# WIFIBT_AP6398S.net
KiCad netlist of a schematic drawn in Altium Designer
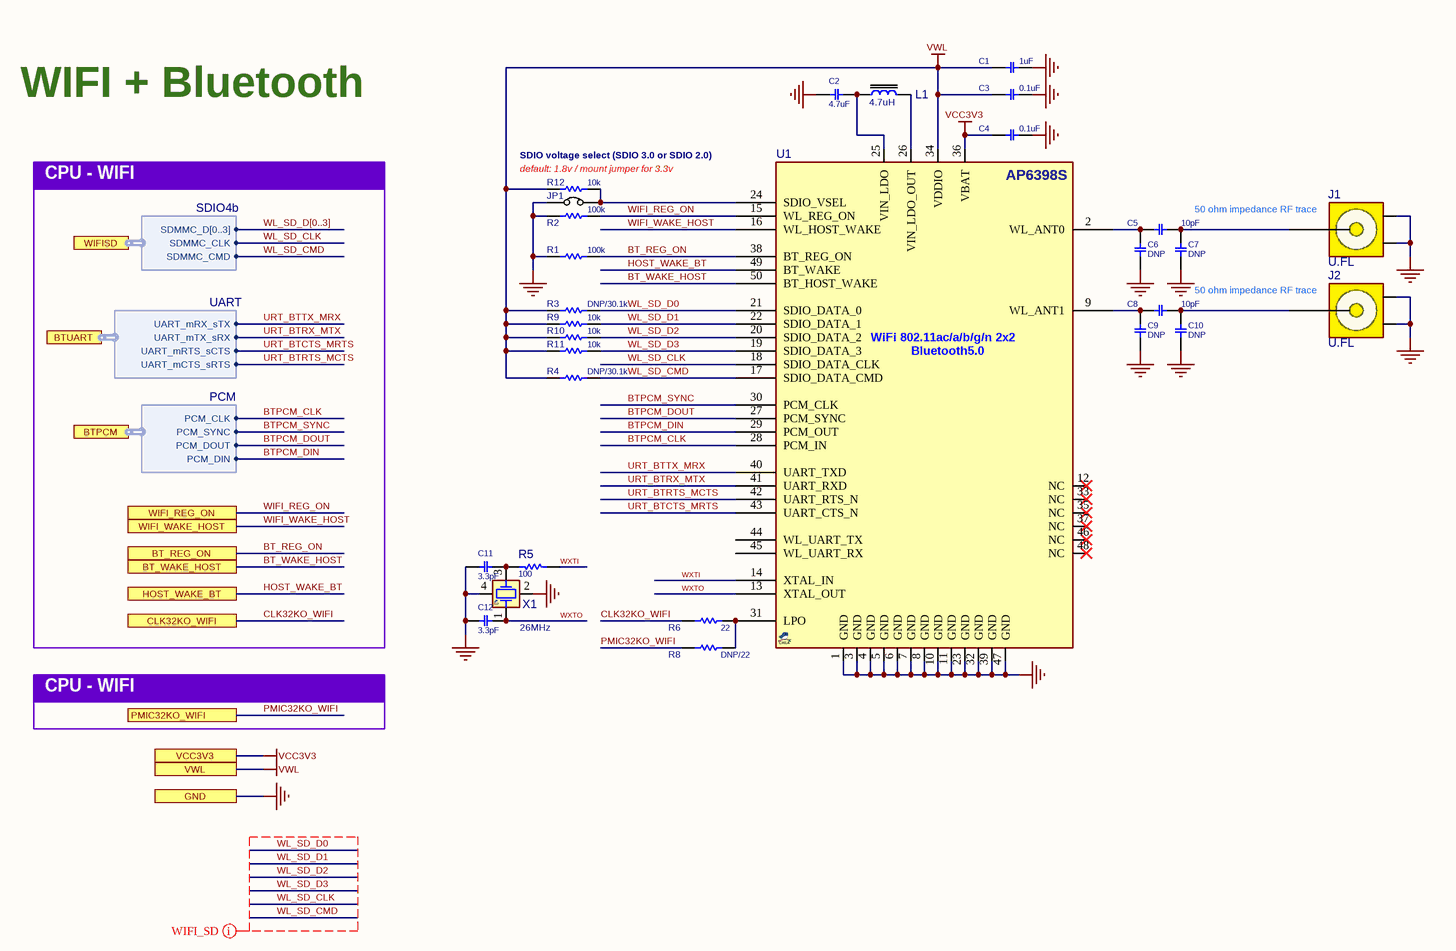
[diagram p0: WIFIBT_AP6398S.SchDoc]

(export (version "E")
  (design (tool "Eeschema 10.0.6"))
  (components
    (comp (ref "C1")
      (value "1uF")
      (footprint "C0402")
      (description "CAP, MLCC")
      (fields (field (name "MANF_P#") "CL05A105KO5NNND") (field (name "MANF") "Samsung"))
      (libsource (lib "passive_smd") (part "CAP_SMD_MLCC"))
    )
    (comp (ref "C2")
      (value "4.7uF")
      (footprint "C0402")
      (description "CAP, MLCC")
      (fields (field (name "MANF_P#") "LMK105BBJ475MVLF") (field (name "MANF") "Taiyo Yuden"))
      (libsource (lib "passive_smd") (part "CAP_SMD_MLCC"))
    )
    (comp (ref "C3")
      (value "0.1uF")
      (footprint "C0402")
      (description "CAP, MLCC")
      (fields (field (name "MANF_P#") "GRM155R61E104") (field (name "MANF") "Murata"))
      (libsource (lib "passive_smd") (part "CAP_SMD_MLCC"))
    )
    (comp (ref "C4")
      (value "0.1uF")
      (footprint "C0402")
      (description "CAP, MLCC")
      (fields (field (name "MANF_P#") "GRM155R61E104") (field (name "MANF") "Murata"))
      (libsource (lib "passive_smd") (part "CAP_SMD_MLCC"))
    )
    (comp (ref "C5")
      (value "10pF")
      (footprint "C0402")
      (description "CAP, MLCC")
      (fields (field (name "MANF_P#") "CC0402JRNPO9BN100") (field (name "MANF") "YAGEO"))
      (libsource (lib "passive_smd") (part "CAP_SMD_MLCC"))
    )
    (comp (ref "C6")
      (value "DNP")
      (footprint "C0402")
      (description "CAP, MLCC, 1nF, 50V, C0G, 10%, 0402")
      (libsource (lib "passive_smd") (part "CAP_SMD_MLCC"))
    )
    (comp (ref "C7")
      (value "DNP")
      (footprint "C0402")
      (description "CAP, MLCC, 1nF, 50V, C0G, 10%, 0402")
      (libsource (lib "passive_smd") (part "CAP_SMD_MLCC"))
    )
    (comp (ref "C8")
      (value "10pF")
      (footprint "C0402")
      (description "CAP, MLCC")
      (fields (field (name "MANF_P#") "CC0402JRNPO9BN100") (field (name "MANF") "YAGEO"))
      (libsource (lib "passive_smd") (part "CAP_SMD_MLCC"))
    )
    (comp (ref "C9")
      (value "DNP")
      (footprint "C0402")
      (description "CAP, MLCC, 1nF, 50V, C0G, 10%, 0402")
      (libsource (lib "passive_smd") (part "CAP_SMD_MLCC"))
    )
    (comp (ref "C10")
      (value "DNP")
      (footprint "C0402")
      (description "CAP, MLCC, 1nF, 50V, C0G, 10%, 0402")
      (libsource (lib "passive_smd") (part "CAP_SMD_MLCC"))
    )
    (comp (ref "C11")
      (value "3.3pF")
      (footprint "C0402")
      (description "CAP, MLCC")
      (fields (field (name "MANF_P#") "CC0402CRNPO9BN3R3") (field (name "MANF") "Yageo"))
      (libsource (lib "passive_smd") (part "CAP_SMD_MLCC"))
    )
    (comp (ref "C12")
      (value "3.3pF")
      (footprint "C0402")
      (description "CAP, MLCC")
      (fields (field (name "MANF_P#") "CC0402CRNPO9BN3R3") (field (name "MANF") "Yageo"))
      (libsource (lib "passive_smd") (part "CAP_SMD_MLCC"))
    )
    (comp (ref "J1")
      (value "U.FL")
      (footprint "UFL")
      (description "CONN, RF, U.FL, STRAIGHT, Ultra Miniature Coaxial")
      (fields
        (field (name "MANF_P#") "CONUFL001-SMD, U.FL-R-SMT-1(10), 128-0711-201")
        (field (name "MANF") "Linx, Hirose, Cinch")
      )
      (libsource (lib "conn_rf") (part "CONN_RF_UFL"))
    )
    (comp (ref "J2")
      (value "U.FL")
      (footprint "UFL")
      (description "CONN, RF, U.FL, STRAIGHT, Ultra Miniature Coaxial")
      (fields
        (field (name "MANF_P#") "CONUFL001-SMD, U.FL-R-SMT-1(10), 128-0711-201")
        (field (name "MANF") "Linx, Hirose, Cinch")
      )
      (libsource (lib "conn_rf") (part "CONN_RF_UFL"))
    )
    (comp (ref "JP1")
      (value "JMPSOLDER")
      (footprint "JP_60X100")
      (description "JUMPER, HEADER 2PIN")
      (fields (field (name "MANF") "MANF") (field (name "MANF_P#") "MANF_P#"))
      (libsource (lib "test-tp_jumper") (part "JUMPER_SOLDER"))
    )
    (comp (ref "L1")
      (value "4.7uH")
      (footprint "L_3")
      (description "INDUCTOR, POWER, SMD")
      (fields (field (name "MANF") "Bourns") (field (name "MANF_P#") "SRN3010-4R7M"))
      (libsource (lib "passive_smd") (part "INDPWR_SMD"))
    )
    (comp (ref "R1")
      (value "100k")
      (footprint "R0402")
      (description "RESISTOR, SMD")
      (libsource (lib "passive_res_smd") (part "RES_SMD"))
    )
    (comp (ref "R2")
      (value "100k")
      (footprint "R0402")
      (description "RESISTOR, SMD")
      (libsource (lib "passive_res_smd") (part "RES_SMD"))
    )
    (comp (ref "R3")
      (value "DNP/30.1k")
      (footprint "R0402")
      (description "RESISTOR, SMD")
      (libsource (lib "passive_res_smd") (part "RES_SMD"))
    )
    (comp (ref "R4")
      (value "DNP/30.1k")
      (footprint "R0402")
      (description "RESISTOR, SMD")
      (libsource (lib "passive_res_smd") (part "RES_SMD"))
    )
    (comp (ref "R5")
      (value "100")
      (footprint "R0402")
      (description "RESISTOR, SMD")
      (libsource (lib "passive_res_smd") (part "RES_SMD"))
    )
    (comp (ref "R6")
      (value "22")
      (footprint "R0402")
      (description "RESISTOR, SMD")
      (libsource (lib "passive_res_smd") (part "RES_SMD"))
    )
    (comp (ref "R8")
      (value "DNP/22")
      (footprint "R0402")
      (description "RESISTOR, SMD")
      (libsource (lib "passive_res_smd") (part "RES_SMD"))
    )
    (comp (ref "R9")
      (value "10k")
      (footprint "R0402")
      (description "RESISTOR, SMD")
      (libsource (lib "passive_res_smd") (part "RES_SMD"))
    )
    (comp (ref "R10")
      (value "10k")
      (footprint "R0402")
      (description "RESISTOR, SMD")
      (libsource (lib "passive_res_smd") (part "RES_SMD"))
    )
    (comp (ref "R11")
      (value "10k")
      (footprint "R0402")
      (description "RESISTOR, SMD")
      (libsource (lib "passive_res_smd") (part "RES_SMD"))
    )
    (comp (ref "R12")
      (value "10k")
      (footprint "R0402")
      (description "RESISTOR, SMD")
      (libsource (lib "passive_res_smd") (part "RES_SMD"))
    )
    (comp (ref "U1")
      (value "AP6398S")
      (footprint "AP6398S_50")
      (description "WiFi with Bluetooth 5.0,")
      (fields (field (name "MANF") "AMPAK"))
      (libsource (lib "module_wifi") (part "AP6398S"))
    )
    (comp (ref "X1")
      (value "26MHz")
      (footprint "XTL_4_2016")
      (description "CRYSTAL")
      (fields (field (name "MANF") "Murata") (field (name "MANF_P#") "XRCGB26M000F2P00R0"))
      (libsource (lib "crystal") (part "XTL_4_40MHz_3225F"))
    )
  )
  (nets
    (net (code "4") (name "/BTPCM_CLK") (class "Default")
      (node (ref "U1") (pin "28") (pinfunction "PCM_IN_28") (pintype "power_in"))
    )
    (net (code "5") (name "/BTPCM_DIN") (class "Default")
      (node (ref "U1") (pin "29") (pinfunction "PCM_OUT_29") (pintype "power_in"))
    )
    (net (code "6") (name "/BTPCM_DOUT") (class "Default")
      (node (ref "U1") (pin "27") (pinfunction "PCM_SYNC_27") (pintype "power_in"))
    )
    (net (code "7") (name "/BTPCM_SYNC") (class "Default")
      (node (ref "U1") (pin "30") (pinfunction "PCM_CLK_30") (pintype "power_in"))
    )
    (net (code "8") (name "/BT_REG_ON") (class "Default")
      (node (ref "R1") (pin "1") (pinfunction "1_1") (pintype "passive"))
      (node (ref "U1") (pin "38") (pinfunction "BT_REG_ON_38") (pintype "power_in"))
    )
    (net (code "9") (name "/BT_WAKE_HOST") (class "Default")
      (node (ref "U1") (pin "50") (pinfunction "BT_HOST_WAKE_50") (pintype "power_in"))
    )
    (net (code "10") (name "/CLK32KO_WIFI") (class "Default")
      (node (ref "R6") (pin "2") (pinfunction "2_2") (pintype "passive"))
    )
    (net (code "11") (name "/HOST_WAKE_BT") (class "Default")
      (node (ref "U1") (pin "49") (pinfunction "BT_WAKE_49") (pintype "power_in"))
    )
    (net (code "12") (name "/PMIC32KO_WIFI") (class "Default")
      (node (ref "R8") (pin "2") (pinfunction "2_2") (pintype "passive"))
    )
    (net (code "13") (name "/URT_BTCTS_MRTS") (class "Default")
      (node (ref "U1") (pin "43") (pinfunction "UART_CTS_N_43") (pintype "power_in"))
    )
    (net (code "14") (name "/URT_BTRTS_MCTS") (class "Default")
      (node (ref "U1") (pin "42") (pinfunction "UART_RTS_N_42") (pintype "power_in"))
    )
    (net (code "15") (name "/URT_BTRX_MTX") (class "Default")
      (node (ref "U1") (pin "41") (pinfunction "UART_RXD_41") (pintype "power_in"))
    )
    (net (code "16") (name "/URT_BTTX_MRX") (class "Default")
      (node (ref "U1") (pin "40") (pinfunction "UART_TXD_40") (pintype "power_in"))
    )
    (net (code "18") (name "/WIFI_REG_ON") (class "Default")
      (node (ref "R2") (pin "1") (pinfunction "1_1") (pintype "passive"))
      (node (ref "U1") (pin "15") (pinfunction "WL_REG_ON_15") (pintype "power_in"))
    )
    (net (code "19") (name "/WIFI_WAKE_HOST") (class "Default")
      (node (ref "U1") (pin "16") (pinfunction "WL_HOST_WAKE_16") (pintype "power_in"))
    )
    (net (code "20") (name "/WL_SD_CLK") (class "Default")
      (node (ref "U1") (pin "18") (pinfunction "SDIO_DATA_CLK_18") (pintype "power_in"))
    )
    (net (code "21") (name "/WL_SD_CMD") (class "Default")
      (node (ref "R4") (pin "1") (pinfunction "1_1") (pintype "passive"))
      (node (ref "U1") (pin "17") (pinfunction "SDIO_DATA_CMD_17") (pintype "power_in"))
    )
    (net (code "22") (name "/WL_SD_D0") (class "Default")
      (node (ref "R3") (pin "1") (pinfunction "1_1") (pintype "passive"))
      (node (ref "U1") (pin "21") (pinfunction "SDIO_DATA_0_21") (pintype "power_in"))
    )
    (net (code "23") (name "/WL_SD_D1") (class "Default")
      (node (ref "R9") (pin "1") (pinfunction "1_1") (pintype "passive"))
      (node (ref "U1") (pin "22") (pinfunction "SDIO_DATA_1_22") (pintype "power_in"))
    )
    (net (code "24") (name "/WL_SD_D2") (class "Default")
      (node (ref "R10") (pin "1") (pinfunction "1_1") (pintype "passive"))
      (node (ref "U1") (pin "20") (pinfunction "SDIO_DATA_2_20") (pintype "power_in"))
    )
    (net (code "25") (name "/WL_SD_D3") (class "Default")
      (node (ref "R11") (pin "1") (pinfunction "1_1") (pintype "passive"))
      (node (ref "U1") (pin "19") (pinfunction "SDIO_DATA_3_19") (pintype "power_in"))
    )
    (net (code "26") (name "/WXTI") (class "Default")
      (node (ref "R5") (pin "2") (pinfunction "2_2") (pintype "passive"))
      (node (ref "U1") (pin "14") (pinfunction "XTAL_IN_14") (pintype "power_in"))
    )
    (net (code "27") (name "/WXTO") (class "Default")
      (node (ref "C12") (pin "1") (pinfunction "1_1") (pintype "passive"))
      (node (ref "U1") (pin "13") (pinfunction "XTAL_OUT_13") (pintype "power_in"))
      (node (ref "X1") (pin "1") (pinfunction "XA_1") (pintype "passive"))
    )
    (net (code "31") (name "GND") (class "Default")
      (node (ref "C1") (pin "1") (pinfunction "1_1") (pintype "passive"))
      (node (ref "C10") (pin "2") (pinfunction "2_2") (pintype "passive"))
      (node (ref "C11") (pin "2") (pinfunction "2_2") (pintype "passive"))
      (node (ref "C12") (pin "2") (pinfunction "2_2") (pintype "passive"))
      (node (ref "C2") (pin "2") (pinfunction "2_2") (pintype "passive"))
      (node (ref "C3") (pin "1") (pinfunction "1_1") (pintype "passive"))
      (node (ref "C4") (pin "1") (pinfunction "1_1") (pintype "passive"))
      (node (ref "C6") (pin "2") (pinfunction "2_2") (pintype "passive"))
      (node (ref "C7") (pin "2") (pinfunction "2_2") (pintype "passive"))
      (node (ref "C9") (pin "2") (pinfunction "2_2") (pintype "passive"))
      (node (ref "J1") (pin "2") (pinfunction "G1_2") (pintype "passive"))
      (node (ref "J1") (pin "3") (pinfunction "G2_3") (pintype "passive"))
      (node (ref "J2") (pin "2") (pinfunction "G1_2") (pintype "passive"))
      (node (ref "J2") (pin "3") (pinfunction "G2_3") (pintype "passive"))
      (node (ref "JP1") (pin "1") (pinfunction "1_1") (pintype "passive"))
      (node (ref "R1") (pin "2") (pinfunction "2_2") (pintype "passive"))
      (node (ref "R2") (pin "2") (pinfunction "2_2") (pintype "passive"))
      (node (ref "U1") (pin "1") (pinfunction "GND_1") (pintype "power_in"))
      (node (ref "U1") (pin "10") (pinfunction "GND_10") (pintype "power_in"))
      (node (ref "U1") (pin "11") (pinfunction "GND_11") (pintype "power_in"))
      (node (ref "U1") (pin "23") (pinfunction "GND_23") (pintype "power_in"))
      (node (ref "U1") (pin "3") (pinfunction "GND_3") (pintype "power_in"))
      (node (ref "U1") (pin "32") (pinfunction "GND_32") (pintype "power_in"))
      (node (ref "U1") (pin "39") (pinfunction "GND_39") (pintype "power_in"))
      (node (ref "U1") (pin "4") (pinfunction "GND_4") (pintype "power_in"))
      (node (ref "U1") (pin "47") (pinfunction "GND_47") (pintype "power_in"))
      (node (ref "U1") (pin "5") (pinfunction "GND_5") (pintype "power_in"))
      (node (ref "U1") (pin "6") (pinfunction "GND_6") (pintype "power_in"))
      (node (ref "U1") (pin "7") (pinfunction "GND_7") (pintype "power_in"))
      (node (ref "U1") (pin "8") (pinfunction "GND_8") (pintype "power_in"))
      (node (ref "X1") (pin "2") (pinfunction "GND1_2") (pintype "passive"))
      (node (ref "X1") (pin "4") (pinfunction "GND2_4") (pintype "passive"))
    )
    (net (code "32") (name "Net-(J1-SIG)") (class "Default")
      (node (ref "C5") (pin "1") (pinfunction "1_1") (pintype "passive"))
      (node (ref "C7") (pin "1") (pinfunction "1_1") (pintype "passive"))
      (node (ref "J1") (pin "1") (pinfunction "SIG_1") (pintype "passive"))
    )
    (net (code "33") (name "Net-(J2-SIG)") (class "Default")
      (node (ref "C10") (pin "1") (pinfunction "1_1") (pintype "passive"))
      (node (ref "C8") (pin "1") (pinfunction "1_1") (pintype "passive"))
      (node (ref "J2") (pin "1") (pinfunction "SIG_1") (pintype "passive"))
    )
    (net (code "34") (name "Net-(U1-LPO)") (class "Default")
      (node (ref "R6") (pin "1") (pinfunction "1_1") (pintype "passive"))
      (node (ref "R8") (pin "1") (pinfunction "1_1") (pintype "passive"))
      (node (ref "U1") (pin "31") (pinfunction "LPO_31") (pintype "power_in"))
    )
    (net (code "35") (name "Net-(U1-SDIO_VSEL)") (class "Default")
      (node (ref "JP1") (pin "2") (pinfunction "2_2") (pintype "passive"))
      (node (ref "R12") (pin "1") (pinfunction "1_1") (pintype "passive"))
      (node (ref "U1") (pin "24") (pinfunction "SDIO_VSEL_24") (pintype "power_in"))
    )
    (net (code "36") (name "Net-(U1-VIN_LDO)") (class "Default")
      (node (ref "C2") (pin "1") (pinfunction "1_1") (pintype "passive"))
      (node (ref "L1") (pin "1") (pinfunction "1_1") (pintype "passive"))
      (node (ref "U1") (pin "25") (pinfunction "VIN_LDO_25") (pintype "power_in"))
    )
    (net (code "37") (name "Net-(U1-VIN_LDO_OUT)") (class "Default")
      (node (ref "L1") (pin "2") (pinfunction "2_2") (pintype "passive"))
      (node (ref "U1") (pin "26") (pinfunction "VIN_LDO_OUT_26") (pintype "power_in"))
    )
    (net (code "38") (name "Net-(U1-WL_ANT0)") (class "Default")
      (node (ref "C5") (pin "2") (pinfunction "2_2") (pintype "passive"))
      (node (ref "C6") (pin "1") (pinfunction "1_1") (pintype "passive"))
      (node (ref "U1") (pin "2") (pinfunction "WL_ANT0_2") (pintype "power_in"))
    )
    (net (code "39") (name "Net-(U1-WL_ANT1)") (class "Default")
      (node (ref "C8") (pin "2") (pinfunction "2_2") (pintype "passive"))
      (node (ref "C9") (pin "1") (pinfunction "1_1") (pintype "passive"))
      (node (ref "U1") (pin "9") (pinfunction "WL_ANT1_9") (pintype "power_in"))
    )
    (net (code "40") (name "Net-(X1-XB)") (class "Default")
      (node (ref "C11") (pin "1") (pinfunction "1_1") (pintype "passive"))
      (node (ref "R5") (pin "1") (pinfunction "1_1") (pintype "passive"))
      (node (ref "X1") (pin "3") (pinfunction "XB_3") (pintype "passive"))
    )
    (net (code "41") (name "VCC3V3") (class "Default")
      (node (ref "C4") (pin "2") (pinfunction "2_2") (pintype "passive"))
      (node (ref "U1") (pin "36") (pinfunction "VBAT_36") (pintype "power_in"))
    )
    (net (code "42") (name "VWL") (class "Default")
      (node (ref "C1") (pin "2") (pinfunction "2_2") (pintype "passive"))
      (node (ref "C3") (pin "2") (pinfunction "2_2") (pintype "passive"))
      (node (ref "R10") (pin "2") (pinfunction "2_2") (pintype "passive"))
      (node (ref "R11") (pin "2") (pinfunction "2_2") (pintype "passive"))
      (node (ref "R12") (pin "2") (pinfunction "2_2") (pintype "passive"))
      (node (ref "R3") (pin "2") (pinfunction "2_2") (pintype "passive"))
      (node (ref "R4") (pin "2") (pinfunction "2_2") (pintype "passive"))
      (node (ref "R9") (pin "2") (pinfunction "2_2") (pintype "passive"))
      (node (ref "U1") (pin "34") (pinfunction "VDDIO_34") (pintype "power_in"))
    )
    (net (code "43") (name "unconnected-(U1-NC-Pad12)") (class "Default")
      (node (ref "U1") (pin "12") (pinfunction "NC_12") (pintype "power_in+no_connect"))
    )
    (net (code "44") (name "unconnected-(U1-NC-Pad33)") (class "Default")
      (node (ref "U1") (pin "33") (pinfunction "NC_33") (pintype "power_in+no_connect"))
    )
    (net (code "45") (name "unconnected-(U1-NC-Pad35)") (class "Default")
      (node (ref "U1") (pin "35") (pinfunction "NC_35") (pintype "power_in+no_connect"))
    )
    (net (code "46") (name "unconnected-(U1-NC-Pad37)") (class "Default")
      (node (ref "U1") (pin "37") (pinfunction "NC_37") (pintype "power_in+no_connect"))
    )
    (net (code "47") (name "unconnected-(U1-NC-Pad46)") (class "Default")
      (node (ref "U1") (pin "46") (pinfunction "NC_46") (pintype "power_in+no_connect"))
    )
    (net (code "48") (name "unconnected-(U1-NC-Pad48)") (class "Default")
      (node (ref "U1") (pin "48") (pinfunction "NC_48") (pintype "power_in+no_connect"))
    )
    (net (code "49") (name "unconnected-(U1-WL_UART_RX-Pad45)") (class "Default")
      (node (ref "U1") (pin "45") (pinfunction "WL_UART_RX_45") (pintype "power_in"))
    )
    (net (code "50") (name "unconnected-(U1-WL_UART_TX-Pad44)") (class "Default")
      (node (ref "U1") (pin "44") (pinfunction "WL_UART_TX_44") (pintype "power_in"))
    )
  )
)
